# IO_Board.net
KiCad netlist of a schematic drawn in Altium Designer
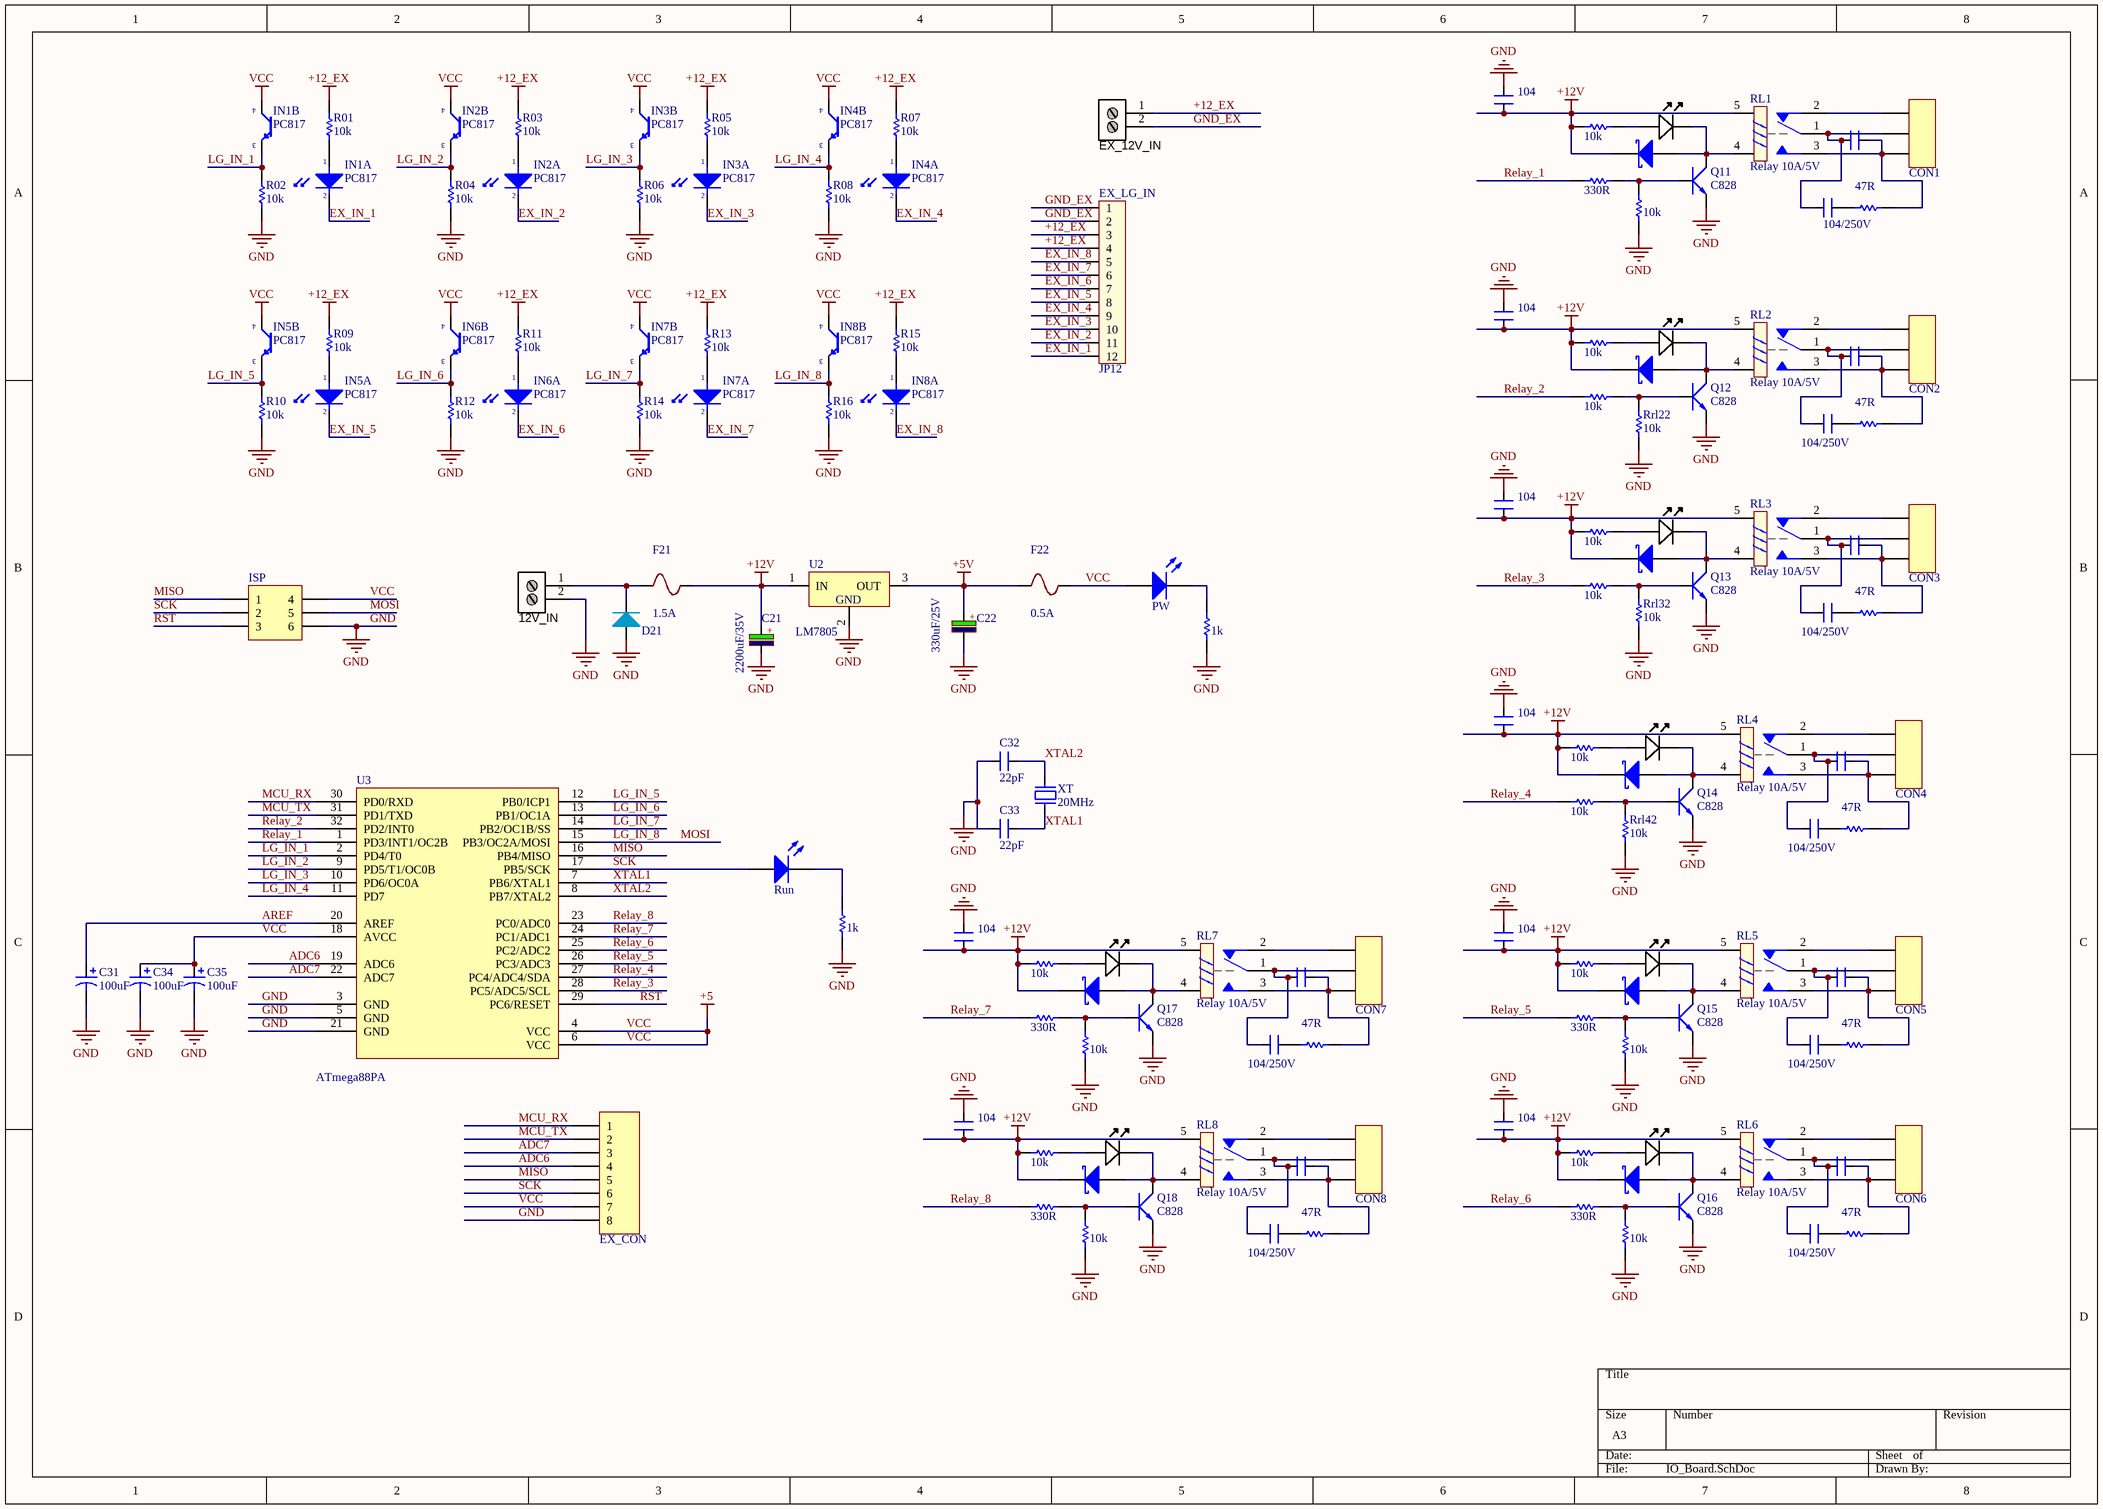
[diagram p0: IO_Board.SchDoc]

(export (version "E")
  (design (tool "Eeschema 10.0.6"))
  (components
    (comp (ref "12V_IN")
      (value "Stackable ScrewTerm")
      (footprint "2P_PCB_ScrewTerm_200mil")
      (description "Terminal Block Screw Type THT 2-Position 3.81mm pitch")
      (libsource (lib "PBL - Connectors") (part "2P_ScrewTerm_90S_3.81MM"))
    )
    (comp (ref "C21")
      (value "2200uF/35V")
      (footprint "heromap:CP_1000uF_25V")
      (description "Cap 1000uF/16V - 220uF/50V")
      (libsource (lib "heromap") (part "CP4"))
    )
    (comp (ref "C22")
      (value "330uF/25V")
      (footprint "heromap:CP1.5/3.4")
      (description "Cap 1000uF/16V - 220uF/50V")
      (libsource (lib "heromap") (part "CP4"))
    )
    (comp (ref "C31")
      (value "100uF")
      (footprint "CAPC2012N_F")
      (fields (field (name "Comment") "Cap"))
      (libsource (lib "Tuan") (part "Cap"))
    )
    (comp (ref "C32")
      (value "22pF")
      (footprint "CAPC1608N")
      (fields (field (name "Comment") "CAP NP"))
      (libsource (lib "Tuan") (part "CAP NP"))
    )
    (comp (ref "C33")
      (value "22pF")
      (footprint "CAPC1608N")
      (fields (field (name "Comment") "CAP NP"))
      (libsource (lib "Tuan") (part "CAP NP"))
    )
    (comp (ref "C34")
      (value "100uF")
      (footprint "CAPC2012N_F")
      (fields (field (name "Comment") "Cap"))
      (libsource (lib "Tuan") (part "Cap"))
    )
    (comp (ref "C35")
      (value "100uF")
      (footprint "CAPC2012N_F")
      (fields (field (name "Comment") "Cap"))
      (libsource (lib "Tuan") (part "Cap"))
    )
    (comp (ref "CON1")
      (value "3P_ScrewTerm_200mil")
      (footprint "3P_ScrewTerm_200mil")
      (libsource (lib "Tuan") (part "3P_ScrewTerm_200mil"))
    )
    (comp (ref "CON2")
      (value "3P_ScrewTerm_200mil")
      (footprint "3P_ScrewTerm_200mil")
      (libsource (lib "Tuan") (part "3P_ScrewTerm_200mil"))
    )
    (comp (ref "CON3")
      (value "3P_ScrewTerm_200mil")
      (footprint "3P_ScrewTerm_200mil")
      (libsource (lib "Tuan") (part "3P_ScrewTerm_200mil"))
    )
    (comp (ref "CON4")
      (value "3P_ScrewTerm_200mil")
      (footprint "3P_ScrewTerm_200mil")
      (libsource (lib "Tuan") (part "3P_ScrewTerm_200mil"))
    )
    (comp (ref "CON5")
      (value "3P_ScrewTerm_200mil")
      (footprint "3P_ScrewTerm_200mil")
      (libsource (lib "Tuan") (part "3P_ScrewTerm_200mil"))
    )
    (comp (ref "CON6")
      (value "3P_ScrewTerm_200mil")
      (footprint "3P_ScrewTerm_200mil")
      (libsource (lib "Tuan") (part "3P_ScrewTerm_200mil"))
    )
    (comp (ref "CON7")
      (value "3P_ScrewTerm_200mil")
      (footprint "3P_ScrewTerm_200mil")
      (libsource (lib "Tuan") (part "3P_ScrewTerm_200mil"))
    )
    (comp (ref "CON8")
      (value "3P_ScrewTerm_200mil")
      (footprint "3P_ScrewTerm_200mil")
      (libsource (lib "Tuan") (part "3P_ScrewTerm_200mil"))
    )
    (comp (ref "Crl1")
      (value "104")
      (footprint "CAPC2012N_F")
      (fields (field (name "Comment") "CAP NP"))
      (libsource (lib "Tuan") (part "CAP NP"))
    )
    (comp (ref "Crl2")
      (value "104")
      (footprint "CAPC2012N_F")
      (fields (field (name "Comment") "CAP NP"))
      (libsource (lib "Tuan") (part "CAP NP"))
    )
    (comp (ref "Crl3")
      (value "104")
      (footprint "CAPC2012N_F")
      (fields (field (name "Comment") "CAP NP"))
      (libsource (lib "Tuan") (part "CAP NP"))
    )
    (comp (ref "Crl4")
      (value "104")
      (footprint "CAPC2012N_F")
      (fields (field (name "Comment") "CAP NP"))
      (libsource (lib "Tuan") (part "CAP NP"))
    )
    (comp (ref "Crl5")
      (value "104")
      (footprint "CAPC2012N_F")
      (fields (field (name "Comment") "CAP NP"))
      (libsource (lib "Tuan") (part "CAP NP"))
    )
    (comp (ref "Crl6")
      (value "104")
      (footprint "CAPC2012N_F")
      (fields (field (name "Comment") "CAP NP"))
      (libsource (lib "Tuan") (part "CAP NP"))
    )
    (comp (ref "Crl7")
      (value "104")
      (footprint "CAPC2012N_F")
      (fields (field (name "Comment") "CAP NP"))
      (libsource (lib "Tuan") (part "CAP NP"))
    )
    (comp (ref "Crl8")
      (value "104")
      (footprint "CAPC2012N_F")
      (fields (field (name "Comment") "CAP NP"))
      (libsource (lib "Tuan") (part "CAP NP"))
    )
    (comp (ref "Csub1")
      (value "104/250V")
      (footprint "CAPMF12.5x4.5x9.0x10mmLS")
      (fields (field (name "Comment") "CAP NP"))
      (libsource (lib "Tuan") (part "CAP NP"))
    )
    (comp (ref "Csub2")
      (value "104/250V")
      (footprint "CAPMF12.5x4.5x9.0x10mmLS")
      (fields (field (name "Comment") "CAP NP"))
      (libsource (lib "Tuan") (part "CAP NP"))
    )
    (comp (ref "Csub3")
      (value "104/250V")
      (footprint "CAPMF12.5x4.5x9.0x10mmLS")
      (fields (field (name "Comment") "CAP NP"))
      (libsource (lib "Tuan") (part "CAP NP"))
    )
    (comp (ref "Csub4")
      (value "104/250V")
      (footprint "CAPMF12.5x4.5x9.0x10mmLS")
      (fields (field (name "Comment") "CAP NP"))
      (libsource (lib "Tuan") (part "CAP NP"))
    )
    (comp (ref "Csub5")
      (value "104/250V")
      (footprint "CAPMF12.5x4.5x9.0x10mmLS")
      (fields (field (name "Comment") "CAP NP"))
      (libsource (lib "Tuan") (part "CAP NP"))
    )
    (comp (ref "Csub6")
      (value "104/250V")
      (footprint "CAPMF12.5x4.5x9.0x10mmLS")
      (fields (field (name "Comment") "CAP NP"))
      (libsource (lib "Tuan") (part "CAP NP"))
    )
    (comp (ref "Csub7")
      (value "104/250V")
      (footprint "CAPMF12.5x4.5x9.0x10mmLS")
      (fields (field (name "Comment") "CAP NP"))
      (libsource (lib "Tuan") (part "CAP NP"))
    )
    (comp (ref "Csub8")
      (value "104/250V")
      (footprint "CAPMF12.5x4.5x9.0x10mmLS")
      (fields (field (name "Comment") "CAP NP"))
      (libsource (lib "Tuan") (part "CAP NP"))
    )
    (comp (ref "D11") (value "Diode") (footprint "DO-214AC") (libsource (lib "Tuan") (part "Diode")))
    (comp (ref "D12") (value "Diode") (footprint "DO-214AC") (libsource (lib "Tuan") (part "Diode")))
    (comp (ref "D13") (value "Diode") (footprint "DO-214AC") (libsource (lib "Tuan") (part "Diode")))
    (comp (ref "D14") (value "Diode") (footprint "DO-214AC") (libsource (lib "Tuan") (part "Diode")))
    (comp (ref "D15") (value "Diode") (footprint "DO-214AC") (libsource (lib "Tuan") (part "Diode")))
    (comp (ref "D16") (value "Diode") (footprint "DO-214AC") (libsource (lib "Tuan") (part "Diode")))
    (comp (ref "D17") (value "Diode") (footprint "DO-214AC") (libsource (lib "Tuan") (part "Diode")))
    (comp (ref "D18") (value "Diode") (footprint "DO-214AC") (libsource (lib "Tuan") (part "Diode")))
    (comp (ref "D21") (value "Diode") (footprint "Diode 3A") (libsource (lib "") (part "Diode_1")))
    (comp (ref "E1")
      (value "Blue")
      (footprint "LED-0805-A")
      (description "LED 0805 SMD Blue 100mcd 470nm")
      (libsource (lib "PBL - Light Sources") (part "LED_SMD_Blue_0805_100mcd"))
    )
    (comp (ref "E2")
      (value "Blue")
      (footprint "LED-0805-A")
      (description "LED 0805 SMD Blue 100mcd 470nm")
      (libsource (lib "PBL - Light Sources") (part "LED_SMD_Blue_0805_100mcd"))
    )
    (comp (ref "E3")
      (value "Blue")
      (footprint "LED-0805-A")
      (description "LED 0805 SMD Blue 100mcd 470nm")
      (libsource (lib "PBL - Light Sources") (part "LED_SMD_Blue_0805_100mcd"))
    )
    (comp (ref "E4")
      (value "Blue")
      (footprint "LED-0805-A")
      (description "LED 0805 SMD Blue 100mcd 470nm")
      (libsource (lib "PBL - Light Sources") (part "LED_SMD_Blue_0805_100mcd"))
    )
    (comp (ref "E5")
      (value "Blue")
      (footprint "LED-0805-A")
      (description "LED 0805 SMD Blue 100mcd 470nm")
      (libsource (lib "PBL - Light Sources") (part "LED_SMD_Blue_0805_100mcd"))
    )
    (comp (ref "E6")
      (value "Blue")
      (footprint "LED-0805-A")
      (description "LED 0805 SMD Blue 100mcd 470nm")
      (libsource (lib "PBL - Light Sources") (part "LED_SMD_Blue_0805_100mcd"))
    )
    (comp (ref "E7")
      (value "Blue")
      (footprint "LED-0805-A")
      (description "LED 0805 SMD Blue 100mcd 470nm")
      (libsource (lib "PBL - Light Sources") (part "LED_SMD_Blue_0805_100mcd"))
    )
    (comp (ref "E8")
      (value "Blue")
      (footprint "LED-0805-A")
      (description "LED 0805 SMD Blue 100mcd 470nm")
      (libsource (lib "PBL - Light Sources") (part "LED_SMD_Blue_0805_100mcd"))
    )
    (comp (ref "EX_12V_IN")
      (value "Stackable ScrewTerm")
      (footprint "2P_PCB_ScrewTerm_200mil")
      (description "Terminal Block Screw Type THT 2-Position 3.81mm pitch")
      (libsource (lib "PBL - Connectors") (part "2P_ScrewTerm_90S_3.81MM"))
    )
    (comp (ref "EX_CON")
      (value "Header 8")
      (footprint "heromap:HDR1X8")
      (description "Header, 8-Pin")
      (fields (field (name "PUBLISHER") "Altium Limited"))
      (libsource (lib "heromap") (part "Header 8"))
    )
    (comp (ref "EX_LG_IN")
      (value "JP12")
      (footprint "12P_ScrewTerm_200mil")
      (description "Connector 12")
      (libsource (lib "heromap") (part "Con12"))
    )
    (comp (ref "F21") (value "1.5A") (footprint "FUSE_SR-5-BK") (libsource (lib "Tuan") (part "Fuse")))
    (comp (ref "F22") (value "0.5A") (footprint "RESC2012N_ZERO") (libsource (lib "Tuan") (part "Fuse")))
    (comp (ref "IN1") (value "PC817") (footprint "DIP4/W0.3") (libsource (lib "Tuan") (part "Opto")))
    (comp (ref "IN2") (value "PC817") (footprint "DIP4/W0.3") (libsource (lib "Tuan") (part "Opto")))
    (comp (ref "IN3") (value "PC817") (footprint "DIP4/W0.3") (libsource (lib "Tuan") (part "Opto")))
    (comp (ref "IN4") (value "PC817") (footprint "DIP4/W0.3") (libsource (lib "Tuan") (part "Opto")))
    (comp (ref "IN5") (value "PC817") (footprint "DIP4/W0.3") (libsource (lib "Tuan") (part "Opto")))
    (comp (ref "IN6") (value "PC817") (footprint "DIP4/W0.3") (libsource (lib "Tuan") (part "Opto")))
    (comp (ref "IN7") (value "PC817") (footprint "DIP4/W0.3") (libsource (lib "Tuan") (part "Opto")))
    (comp (ref "IN8") (value "PC817") (footprint "DIP4/W0.3") (libsource (lib "Tuan") (part "Opto")))
    (comp (ref "ISP")
      (value "Header 3X2A")
      (footprint "HDR2X3_CEN")
      (description "Header, 3-Pin, Dual row")
      (fields (field (name "PUBLISHER") "Altium Limited"))
      (libsource (lib "Miscellaneous Connectors") (part "Header 3X2A"))
    )
    (comp (ref "MOV1")
      (value "CAP NP")
      (footprint "CAPC500P450250X550")
      (libsource (lib "Tuan") (part "CAP NP"))
    )
    (comp (ref "MOV2")
      (value "CAP NP")
      (footprint "CAPC500P450250X550")
      (libsource (lib "Tuan") (part "CAP NP"))
    )
    (comp (ref "MOV3")
      (value "CAP NP")
      (footprint "CAPC500P450250X550")
      (libsource (lib "Tuan") (part "CAP NP"))
    )
    (comp (ref "MOV4")
      (value "CAP NP")
      (footprint "CAPC500P450250X550")
      (libsource (lib "Tuan") (part "CAP NP"))
    )
    (comp (ref "MOV5")
      (value "CAP NP")
      (footprint "CAPC500P450250X550")
      (libsource (lib "Tuan") (part "CAP NP"))
    )
    (comp (ref "MOV6")
      (value "CAP NP")
      (footprint "CAPC500P450250X550")
      (libsource (lib "Tuan") (part "CAP NP"))
    )
    (comp (ref "MOV7")
      (value "CAP NP")
      (footprint "CAPC500P450250X550")
      (libsource (lib "Tuan") (part "CAP NP"))
    )
    (comp (ref "MOV8")
      (value "CAP NP")
      (footprint "CAPC500P450250X550")
      (libsource (lib "Tuan") (part "CAP NP"))
    )
    (comp (ref "PW") (value "Led") (footprint "LED 5mm RED") (libsource (lib "Tuan") (part "Led")))
    (comp (ref "Q11")
      (value "C828")
      (footprint "SOT23 TOP")
      (description "Transistor C828 C1815....")
      (libsource (lib "Tuan") (part "NPN"))
    )
    (comp (ref "Q12")
      (value "C828")
      (footprint "SOT23 TOP")
      (description "Transistor C828 C1815....")
      (libsource (lib "Tuan") (part "NPN"))
    )
    (comp (ref "Q13")
      (value "C828")
      (footprint "SOT23 TOP")
      (description "Transistor C828 C1815....")
      (libsource (lib "Tuan") (part "NPN"))
    )
    (comp (ref "Q14")
      (value "C828")
      (footprint "SOT23 TOP")
      (description "Transistor C828 C1815....")
      (libsource (lib "Tuan") (part "NPN"))
    )
    (comp (ref "Q15")
      (value "C828")
      (footprint "SOT23 TOP")
      (description "Transistor C828 C1815....")
      (libsource (lib "Tuan") (part "NPN"))
    )
    (comp (ref "Q16")
      (value "C828")
      (footprint "SOT23 TOP")
      (description "Transistor C828 C1815....")
      (libsource (lib "Tuan") (part "NPN"))
    )
    (comp (ref "Q17")
      (value "C828")
      (footprint "SOT23 TOP")
      (description "Transistor C828 C1815....")
      (libsource (lib "Tuan") (part "NPN"))
    )
    (comp (ref "Q18")
      (value "C828")
      (footprint "SOT23 TOP")
      (description "Transistor C828 C1815....")
      (libsource (lib "Tuan") (part "NPN"))
    )
    (comp (ref "R01")
      (value "10k")
      (footprint "RESC1608N_ZERO")
      (fields (field (name "Comment") "Res"))
      (libsource (lib "Tuan") (part "Res"))
    )
    (comp (ref "R02")
      (value "10k")
      (footprint "RESC1608N_ZERO")
      (fields (field (name "Comment") "Res"))
      (libsource (lib "Tuan") (part "Res"))
    )
    (comp (ref "R03")
      (value "10k")
      (footprint "RESC1608N_ZERO")
      (fields (field (name "Comment") "Res"))
      (libsource (lib "Tuan") (part "Res"))
    )
    (comp (ref "R04")
      (value "10k")
      (footprint "RESC2012N_F")
      (fields (field (name "Comment") "Res"))
      (libsource (lib "Tuan") (part "Res"))
    )
    (comp (ref "R05")
      (value "10k")
      (footprint "RESC2012N_F")
      (fields (field (name "Comment") "Res"))
      (libsource (lib "Tuan") (part "Res"))
    )
    (comp (ref "R06")
      (value "10k")
      (footprint "RESC2012N_F")
      (fields (field (name "Comment") "Res"))
      (libsource (lib "Tuan") (part "Res"))
    )
    (comp (ref "R07")
      (value "10k")
      (footprint "RESC2012N_F")
      (fields (field (name "Comment") "Res"))
      (libsource (lib "Tuan") (part "Res"))
    )
    (comp (ref "R08")
      (value "10k")
      (footprint "RESC2012N_F")
      (fields (field (name "Comment") "Res"))
      (libsource (lib "Tuan") (part "Res"))
    )
    (comp (ref "R09")
      (value "10k")
      (footprint "RESC2012N_F")
      (fields (field (name "Comment") "Res"))
      (libsource (lib "Tuan") (part "Res"))
    )
    (comp (ref "R10")
      (value "10k")
      (footprint "RESC2012N_F")
      (fields (field (name "Comment") "Res"))
      (libsource (lib "Tuan") (part "Res"))
    )
    (comp (ref "R11")
      (value "10k")
      (footprint "RESC2012N_F")
      (fields (field (name "Comment") "Res"))
      (libsource (lib "Tuan") (part "Res"))
    )
    (comp (ref "R12")
      (value "10k")
      (footprint "RESC2012N_F")
      (fields (field (name "Comment") "Res"))
      (libsource (lib "Tuan") (part "Res"))
    )
    (comp (ref "R13")
      (value "10k")
      (footprint "RESC2012N_F")
      (fields (field (name "Comment") "Res"))
      (libsource (lib "Tuan") (part "Res"))
    )
    (comp (ref "R14")
      (value "10k")
      (footprint "RESC2012N_F")
      (fields (field (name "Comment") "Res"))
      (libsource (lib "Tuan") (part "Res"))
    )
    (comp (ref "R15")
      (value "10k")
      (footprint "RESC2012N_F")
      (fields (field (name "Comment") "Res"))
      (libsource (lib "Tuan") (part "Res"))
    )
    (comp (ref "R16")
      (value "10k")
      (footprint "RESC2012N_F")
      (fields (field (name "Comment") "Res"))
      (libsource (lib "Tuan") (part "Res"))
    )
    (comp (ref "R21")
      (value "1k")
      (footprint "RESC2012N_F")
      (fields (field (name "Comment") "Res_0805_1k"))
      (libsource (lib "Tuan") (part "Res"))
    )
    (comp (ref "R31")
      (value "1k")
      (footprint "RESC2012N_F")
      (fields (field (name "Comment") "Res_0805_1k"))
      (libsource (lib "Tuan") (part "Res"))
    )
    (comp (ref "RL1")
      (value "Relay 10A/5V")
      (footprint "RL_5PIN")
      (description "Relay SPDT,10A - 12VDC 5 Pin")
      (libsource (lib "syhaunguyen") (part "Relay 1"))
    )
    (comp (ref "RL2")
      (value "Relay 10A/5V")
      (footprint "RL_5PIN")
      (description "Relay SPDT,10A - 12VDC 5 Pin")
      (libsource (lib "syhaunguyen") (part "Relay 1"))
    )
    (comp (ref "RL3")
      (value "Relay 10A/5V")
      (footprint "RL_5PIN")
      (description "Relay SPDT,10A - 12VDC 5 Pin")
      (libsource (lib "syhaunguyen") (part "Relay 1"))
    )
    (comp (ref "RL4")
      (value "Relay 10A/5V")
      (footprint "RL_5PIN")
      (description "Relay SPDT,10A - 12VDC 5 Pin")
      (libsource (lib "syhaunguyen") (part "Relay 1"))
    )
    (comp (ref "RL5")
      (value "Relay 10A/5V")
      (footprint "RL_5PIN")
      (description "Relay SPDT,10A - 12VDC 5 Pin")
      (libsource (lib "syhaunguyen") (part "Relay 1"))
    )
    (comp (ref "RL6")
      (value "Relay 10A/5V")
      (footprint "RL_5PIN")
      (description "Relay SPDT,10A - 12VDC 5 Pin")
      (libsource (lib "syhaunguyen") (part "Relay 1"))
    )
    (comp (ref "RL7")
      (value "Relay 10A/5V")
      (footprint "RL_5PIN")
      (description "Relay SPDT,10A - 12VDC 5 Pin")
      (libsource (lib "syhaunguyen") (part "Relay 1"))
    )
    (comp (ref "RL8")
      (value "Relay 10A/5V")
      (footprint "RL_5PIN")
      (description "Relay SPDT,10A - 12VDC 5 Pin")
      (libsource (lib "syhaunguyen") (part "Relay 1"))
    )
    (comp (ref "Rl52")
      (value "10k")
      (footprint "RESC1608N_ZERO")
      (fields (field (name "Comment") "Res"))
      (libsource (lib "Tuan") (part "Res"))
    )
    (comp (ref "Rrl11")
      (value "330R")
      (footprint "RESC1608N_ZERO")
      (fields (field (name "Comment") "Res"))
      (libsource (lib "Tuan") (part "Res"))
    )
    (comp (ref "Rrl12")
      (value "10k")
      (footprint "RESC1608N_ZERO")
      (fields (field (name "Comment") "Res"))
      (libsource (lib "Tuan") (part "Res"))
    )
    (comp (ref "Rrl13")
      (value "10k")
      (footprint "RESC1608N_ZERO")
      (fields (field (name "Comment") "Res"))
      (libsource (lib "Tuan") (part "Res"))
    )
    (comp (ref "Rrl21")
      (value "10k")
      (footprint "RESC1608N_ZERO")
      (fields (field (name "Comment") "Res"))
      (libsource (lib "Tuan") (part "Res"))
    )
    (comp (ref "Rrl22")
      (value "10k")
      (footprint "RESC1608N_ZERO")
      (fields (field (name "Comment") "Res"))
      (libsource (lib "Tuan") (part "Res"))
    )
    (comp (ref "Rrl23")
      (value "10k")
      (footprint "RESC1608N_ZERO")
      (fields (field (name "Comment") "Res"))
      (libsource (lib "Tuan") (part "Res"))
    )
    (comp (ref "Rrl31")
      (value "10k")
      (footprint "RESC1608N_ZERO")
      (fields (field (name "Comment") "Res"))
      (libsource (lib "Tuan") (part "Res"))
    )
    (comp (ref "Rrl32")
      (value "10k")
      (footprint "RESC1608N_ZERO")
      (fields (field (name "Comment") "Res"))
      (libsource (lib "Tuan") (part "Res"))
    )
    (comp (ref "Rrl33")
      (value "10k")
      (footprint "RESC1608N_ZERO")
      (fields (field (name "Comment") "Res"))
      (libsource (lib "Tuan") (part "Res"))
    )
    (comp (ref "Rrl41")
      (value "10k")
      (footprint "RESC1608N_ZERO")
      (fields (field (name "Comment") "Res"))
      (libsource (lib "Tuan") (part "Res"))
    )
    (comp (ref "Rrl42")
      (value "10k")
      (footprint "RESC1608N_ZERO")
      (fields (field (name "Comment") "Res"))
      (libsource (lib "Tuan") (part "Res"))
    )
    (comp (ref "Rrl43")
      (value "10k")
      (footprint "RESC1608N_ZERO")
      (fields (field (name "Comment") "Res"))
      (libsource (lib "Tuan") (part "Res"))
    )
    (comp (ref "Rrl51")
      (value "330R")
      (footprint "RESC1608N_ZERO")
      (fields (field (name "Comment") "Res"))
      (libsource (lib "Tuan") (part "Res"))
    )
    (comp (ref "Rrl53")
      (value "10k")
      (footprint "RESC1608N_ZERO")
      (fields (field (name "Comment") "Res"))
      (libsource (lib "Tuan") (part "Res"))
    )
    (comp (ref "Rrl61")
      (value "330R")
      (footprint "RESC1608N_ZERO")
      (fields (field (name "Comment") "Res"))
      (libsource (lib "Tuan") (part "Res"))
    )
    (comp (ref "Rrl62")
      (value "10k")
      (footprint "RESC1608N_ZERO")
      (fields (field (name "Comment") "Res"))
      (libsource (lib "Tuan") (part "Res"))
    )
    (comp (ref "Rrl63")
      (value "10k")
      (footprint "RESC1608N_ZERO")
      (fields (field (name "Comment") "Res"))
      (libsource (lib "Tuan") (part "Res"))
    )
    (comp (ref "Rrl71")
      (value "330R")
      (footprint "RESC1608N_ZERO")
      (fields (field (name "Comment") "Res"))
      (libsource (lib "Tuan") (part "Res"))
    )
    (comp (ref "Rrl72")
      (value "10k")
      (footprint "RESC1608N_ZERO")
      (fields (field (name "Comment") "Res"))
      (libsource (lib "Tuan") (part "Res"))
    )
    (comp (ref "Rrl73")
      (value "10k")
      (footprint "RESC1608N_ZERO")
      (fields (field (name "Comment") "Res"))
      (libsource (lib "Tuan") (part "Res"))
    )
    (comp (ref "Rrl81")
      (value "330R")
      (footprint "RESC1608N_ZERO")
      (fields (field (name "Comment") "Res"))
      (libsource (lib "Tuan") (part "Res"))
    )
    (comp (ref "Rrl82")
      (value "10k")
      (footprint "RESC1608N_ZERO")
      (fields (field (name "Comment") "Res"))
      (libsource (lib "Tuan") (part "Res"))
    )
    (comp (ref "Rrl83")
      (value "10k")
      (footprint "RESC1608N_ZERO")
      (fields (field (name "Comment") "Res"))
      (libsource (lib "Tuan") (part "Res"))
    )
    (comp (ref "Rsub1")
      (value "47R")
      (footprint "RESTH_AXIAL-0.4")
      (fields (field (name "Comment") "Res"))
      (libsource (lib "Tuan") (part "Res"))
    )
    (comp (ref "Rsub2")
      (value "47R")
      (footprint "RESTH_AXIAL-0.4")
      (fields (field (name "Comment") "Res"))
      (libsource (lib "Tuan") (part "Res"))
    )
    (comp (ref "Rsub3")
      (value "47R")
      (footprint "RESTH_AXIAL-0.4")
      (fields (field (name "Comment") "Res"))
      (libsource (lib "Tuan") (part "Res"))
    )
    (comp (ref "Rsub4")
      (value "47R")
      (footprint "RESTH_AXIAL-0.4")
      (fields (field (name "Comment") "Res"))
      (libsource (lib "Tuan") (part "Res"))
    )
    (comp (ref "Rsub5")
      (value "47R")
      (footprint "RESTH_AXIAL-0.4")
      (fields (field (name "Comment") "Res"))
      (libsource (lib "Tuan") (part "Res"))
    )
    (comp (ref "Rsub6")
      (value "47R")
      (footprint "RESTH_AXIAL-0.4")
      (fields (field (name "Comment") "Res"))
      (libsource (lib "Tuan") (part "Res"))
    )
    (comp (ref "Rsub7")
      (value "47R")
      (footprint "RESTH_AXIAL-0.4")
      (fields (field (name "Comment") "Res"))
      (libsource (lib "Tuan") (part "Res"))
    )
    (comp (ref "Rsub8")
      (value "47R")
      (footprint "RESTH_AXIAL-0.4")
      (fields (field (name "Comment") "Res"))
      (libsource (lib "Tuan") (part "Res"))
    )
    (comp (ref "Run") (value "Led") (footprint "LED 5mm RED") (libsource (lib "Tuan") (part "Led")))
    (comp (ref "U2") (value "LM7805") (footprint "TO-220") (libsource (lib "Tuan") (part "LM78xx")))
    (comp (ref "U3")
      (value "ATmega88PA")
      (footprint "32PIN")
      (description "ATmega48/168/328")
      (libsource (lib "Tuan") (part "ATmega48/168/328"))
    )
    (comp (ref "XT") (value "20MHz") (footprint "XT2") (libsource (lib "Tuan") (part "Crystal")))
  )
  (nets
    (net (code "1") (name "+5") (class "Default")
      (node (ref "C34") (pin "1") (pinfunction "1_1") (pintype "passive"))
      (node (ref "C35") (pin "1") (pinfunction "1_1") (pintype "passive"))
      (node (ref "EX_CON") (pin "7") (pinfunction "7_7") (pintype "passive"))
      (node (ref "F22") (pin "2") (pinfunction "2_2") (pintype "passive"))
      (node (ref "IN1") (pin "4") (pinfunction "C_4") (pintype "passive"))
      (node (ref "IN2") (pin "4") (pinfunction "C_4") (pintype "passive"))
      (node (ref "IN3") (pin "4") (pinfunction "C_4") (pintype "passive"))
      (node (ref "IN4") (pin "4") (pinfunction "C_4") (pintype "passive"))
      (node (ref "IN5") (pin "4") (pinfunction "C_4") (pintype "passive"))
      (node (ref "IN6") (pin "4") (pinfunction "C_4") (pintype "passive"))
      (node (ref "IN7") (pin "4") (pinfunction "C_4") (pintype "passive"))
      (node (ref "IN8") (pin "4") (pinfunction "C_4") (pintype "passive"))
      (node (ref "ISP") (pin "4") (pinfunction "4_4") (pintype "passive"))
      (node (ref "PW") (pin "1") (pinfunction "A_1") (pintype "passive"))
      (node (ref "U3") (pin "18") (pinfunction "AVCC_18") (pintype "passive"))
      (node (ref "U3") (pin "4") (pinfunction "VCC_4") (pintype "passive"))
      (node (ref "U3") (pin "6") (pinfunction "VCC_6") (pintype "passive"))
    )
    (net (code "2") (name "+5V") (class "Default")
      (node (ref "C22") (pin "1") (pinfunction "1_1") (pintype "passive"))
      (node (ref "F22") (pin "1") (pinfunction "1_1") (pintype "passive"))
      (node (ref "U2") (pin "3") (pinfunction "OUT_3") (pintype "passive"))
    )
    (net (code "3") (name "+12V") (class "Default")
      (node (ref "C21") (pin "1") (pinfunction "1_1") (pintype "passive"))
      (node (ref "Crl1") (pin "1") (pinfunction "1_1") (pintype "passive"))
      (node (ref "Crl2") (pin "1") (pinfunction "1_1") (pintype "passive"))
      (node (ref "Crl3") (pin "1") (pinfunction "1_1") (pintype "passive"))
      (node (ref "Crl4") (pin "1") (pinfunction "1_1") (pintype "passive"))
      (node (ref "Crl5") (pin "1") (pinfunction "1_1") (pintype "passive"))
      (node (ref "Crl6") (pin "1") (pinfunction "1_1") (pintype "passive"))
      (node (ref "Crl7") (pin "1") (pinfunction "1_1") (pintype "passive"))
      (node (ref "Crl8") (pin "1") (pinfunction "1_1") (pintype "passive"))
      (node (ref "D11") (pin "2") (pinfunction "K_2") (pintype "passive"))
      (node (ref "D12") (pin "2") (pinfunction "K_2") (pintype "passive"))
      (node (ref "D13") (pin "2") (pinfunction "K_2") (pintype "passive"))
      (node (ref "D14") (pin "2") (pinfunction "K_2") (pintype "passive"))
      (node (ref "D15") (pin "2") (pinfunction "K_2") (pintype "passive"))
      (node (ref "D16") (pin "2") (pinfunction "K_2") (pintype "passive"))
      (node (ref "D17") (pin "2") (pinfunction "K_2") (pintype "passive"))
      (node (ref "D18") (pin "2") (pinfunction "K_2") (pintype "passive"))
      (node (ref "F21") (pin "2") (pinfunction "2_2") (pintype "passive"))
      (node (ref "RL1") (pin "5") (pinfunction "5_5") (pintype "passive"))
      (node (ref "RL2") (pin "5") (pinfunction "5_5") (pintype "passive"))
      (node (ref "RL3") (pin "5") (pinfunction "5_5") (pintype "passive"))
      (node (ref "RL4") (pin "5") (pinfunction "5_5") (pintype "passive"))
      (node (ref "RL5") (pin "5") (pinfunction "5_5") (pintype "passive"))
      (node (ref "RL6") (pin "5") (pinfunction "5_5") (pintype "passive"))
      (node (ref "RL7") (pin "5") (pinfunction "5_5") (pintype "passive"))
      (node (ref "RL8") (pin "5") (pinfunction "5_5") (pintype "passive"))
      (node (ref "Rrl13") (pin "2") (pinfunction "2_2") (pintype "passive"))
      (node (ref "Rrl23") (pin "2") (pinfunction "2_2") (pintype "passive"))
      (node (ref "Rrl33") (pin "2") (pinfunction "2_2") (pintype "passive"))
      (node (ref "Rrl43") (pin "2") (pinfunction "2_2") (pintype "passive"))
      (node (ref "Rrl53") (pin "2") (pinfunction "2_2") (pintype "passive"))
      (node (ref "Rrl63") (pin "2") (pinfunction "2_2") (pintype "passive"))
      (node (ref "Rrl73") (pin "2") (pinfunction "2_2") (pintype "passive"))
      (node (ref "Rrl83") (pin "2") (pinfunction "2_2") (pintype "passive"))
      (node (ref "U2") (pin "1") (pinfunction "IN_1") (pintype "passive"))
    )
    (net (code "4") (name "+12_EX") (class "Default")
      (node (ref "EX_12V_IN") (pin "1") (pinfunction "1_1") (pintype "passive"))
      (node (ref "EX_LG_IN") (pin "3") (pinfunction "3_3") (pintype "passive"))
      (node (ref "EX_LG_IN") (pin "4") (pinfunction "4_4") (pintype "passive"))
      (node (ref "R01") (pin "2") (pinfunction "2_2") (pintype "passive"))
      (node (ref "R03") (pin "2") (pinfunction "2_2") (pintype "passive"))
      (node (ref "R05") (pin "2") (pinfunction "2_2") (pintype "passive"))
      (node (ref "R07") (pin "2") (pinfunction "2_2") (pintype "passive"))
      (node (ref "R09") (pin "2") (pinfunction "2_2") (pintype "passive"))
      (node (ref "R11") (pin "2") (pinfunction "2_2") (pintype "passive"))
      (node (ref "R13") (pin "2") (pinfunction "2_2") (pintype "passive"))
      (node (ref "R15") (pin "2") (pinfunction "2_2") (pintype "passive"))
    )
    (net (code "5") (name "/ADC6") (class "Default")
      (node (ref "EX_CON") (pin "4") (pinfunction "4_4") (pintype "passive"))
      (node (ref "U3") (pin "19") (pinfunction "ADC6_19") (pintype "passive"))
    )
    (net (code "6") (name "/ADC7") (class "Default")
      (node (ref "EX_CON") (pin "3") (pinfunction "3_3") (pintype "passive"))
      (node (ref "U3") (pin "22") (pinfunction "ADC7_22") (pintype "passive"))
    )
    (net (code "7") (name "/AREF") (class "Default")
      (node (ref "C31") (pin "1") (pinfunction "1_1") (pintype "passive"))
      (node (ref "U3") (pin "20") (pinfunction "AREF_20") (pintype "passive"))
    )
    (net (code "8") (name "/EX_IN_1") (class "Default")
      (node (ref "EX_LG_IN") (pin "12") (pinfunction "12_12") (pintype "passive"))
      (node (ref "IN1") (pin "2") (pinfunction "K_2") (pintype "passive"))
    )
    (net (code "9") (name "/EX_IN_2") (class "Default")
      (node (ref "EX_LG_IN") (pin "11") (pinfunction "11_11") (pintype "passive"))
      (node (ref "IN2") (pin "2") (pinfunction "K_2") (pintype "passive"))
    )
    (net (code "10") (name "/EX_IN_3") (class "Default")
      (node (ref "EX_LG_IN") (pin "10") (pinfunction "10_10") (pintype "passive"))
      (node (ref "IN3") (pin "2") (pinfunction "K_2") (pintype "passive"))
    )
    (net (code "11") (name "/EX_IN_4") (class "Default")
      (node (ref "EX_LG_IN") (pin "9") (pinfunction "9_9") (pintype "passive"))
      (node (ref "IN4") (pin "2") (pinfunction "K_2") (pintype "passive"))
    )
    (net (code "12") (name "/EX_IN_5") (class "Default")
      (node (ref "EX_LG_IN") (pin "8") (pinfunction "8_8") (pintype "passive"))
      (node (ref "IN5") (pin "2") (pinfunction "K_2") (pintype "passive"))
    )
    (net (code "13") (name "/EX_IN_6") (class "Default")
      (node (ref "EX_LG_IN") (pin "7") (pinfunction "7_7") (pintype "passive"))
      (node (ref "IN6") (pin "2") (pinfunction "K_2") (pintype "passive"))
    )
    (net (code "14") (name "/EX_IN_7") (class "Default")
      (node (ref "EX_LG_IN") (pin "6") (pinfunction "6_6") (pintype "passive"))
      (node (ref "IN7") (pin "2") (pinfunction "K_2") (pintype "passive"))
    )
    (net (code "15") (name "/EX_IN_8") (class "Default")
      (node (ref "EX_LG_IN") (pin "5") (pinfunction "5_5") (pintype "passive"))
      (node (ref "IN8") (pin "2") (pinfunction "K_2") (pintype "passive"))
    )
    (net (code "16") (name "/GND_EX") (class "Default")
      (node (ref "EX_12V_IN") (pin "2") (pinfunction "2_2") (pintype "passive"))
      (node (ref "EX_LG_IN") (pin "1") (pinfunction "1_1") (pintype "passive"))
      (node (ref "EX_LG_IN") (pin "2") (pinfunction "2_2") (pintype "passive"))
    )
    (net (code "17") (name "/LG_IN_1") (class "Default")
      (node (ref "IN1") (pin "3") (pinfunction "E_3") (pintype "passive"))
      (node (ref "R02") (pin "2") (pinfunction "2_2") (pintype "passive"))
      (node (ref "U3") (pin "2") (pinfunction "PD4/T0_2") (pintype "passive"))
    )
    (net (code "18") (name "/LG_IN_2") (class "Default")
      (node (ref "IN2") (pin "3") (pinfunction "E_3") (pintype "passive"))
      (node (ref "R04") (pin "2") (pinfunction "2_2") (pintype "passive"))
      (node (ref "U3") (pin "9") (pinfunction "PD5/T1/OC0B_9") (pintype "passive"))
    )
    (net (code "19") (name "/LG_IN_3") (class "Default")
      (node (ref "IN3") (pin "3") (pinfunction "E_3") (pintype "passive"))
      (node (ref "R06") (pin "2") (pinfunction "2_2") (pintype "passive"))
      (node (ref "U3") (pin "10") (pinfunction "PD6/OC0A_10") (pintype "passive"))
    )
    (net (code "20") (name "/LG_IN_4") (class "Default")
      (node (ref "IN4") (pin "3") (pinfunction "E_3") (pintype "passive"))
      (node (ref "R08") (pin "2") (pinfunction "2_2") (pintype "passive"))
      (node (ref "U3") (pin "11") (pinfunction "PD7_11") (pintype "passive"))
    )
    (net (code "21") (name "/LG_IN_5") (class "Default")
      (node (ref "IN5") (pin "3") (pinfunction "E_3") (pintype "passive"))
      (node (ref "R10") (pin "2") (pinfunction "2_2") (pintype "passive"))
      (node (ref "U3") (pin "12") (pinfunction "PB0/ICP1_12") (pintype "passive"))
    )
    (net (code "22") (name "/LG_IN_6") (class "Default")
      (node (ref "IN6") (pin "3") (pinfunction "E_3") (pintype "passive"))
      (node (ref "R12") (pin "2") (pinfunction "2_2") (pintype "passive"))
      (node (ref "U3") (pin "13") (pinfunction "PB1/OC1A_13") (pintype "passive"))
    )
    (net (code "23") (name "/LG_IN_7") (class "Default")
      (node (ref "IN7") (pin "3") (pinfunction "E_3") (pintype "passive"))
      (node (ref "R14") (pin "2") (pinfunction "2_2") (pintype "passive"))
      (node (ref "U3") (pin "14") (pinfunction "PB2/OC1B/SS_14") (pintype "passive"))
    )
    (net (code "24") (name "/LG_IN_8") (class "Default")
      (node (ref "IN8") (pin "3") (pinfunction "E_3") (pintype "passive"))
      (node (ref "ISP") (pin "5") (pinfunction "5_5") (pintype "passive"))
      (node (ref "R16") (pin "2") (pinfunction "2_2") (pintype "passive"))
      (node (ref "U3") (pin "15") (pinfunction "PB3/OC2A/MOSI_15") (pintype "passive"))
    )
    (net (code "25") (name "/MCU_RX") (class "Default")
      (node (ref "EX_CON") (pin "1") (pinfunction "1_1") (pintype "passive"))
      (node (ref "U3") (pin "30") (pinfunction "PD0/RXD_30") (pintype "passive"))
    )
    (net (code "26") (name "/MCU_TX") (class "Default")
      (node (ref "EX_CON") (pin "2") (pinfunction "2_2") (pintype "passive"))
      (node (ref "U3") (pin "31") (pinfunction "PD1/TXD_31") (pintype "passive"))
    )
    (net (code "27") (name "/MISO") (class "Default")
      (node (ref "EX_CON") (pin "5") (pinfunction "5_5") (pintype "passive"))
      (node (ref "ISP") (pin "1") (pinfunction "1_1") (pintype "passive"))
      (node (ref "U3") (pin "16") (pinfunction "PB4/MISO_16") (pintype "passive"))
    )
    (net (code "28") (name "/RST") (class "Default")
      (node (ref "ISP") (pin "3") (pinfunction "3_3") (pintype "passive"))
      (node (ref "U3") (pin "29") (pinfunction "PC6/RESET_29") (pintype "passive"))
    )
    (net (code "29") (name "/Relay_1") (class "Default")
      (node (ref "Rrl11") (pin "1") (pinfunction "1_1") (pintype "passive"))
      (node (ref "U3") (pin "1") (pinfunction "PD3/INT1/OC2B_1") (pintype "passive"))
    )
    (net (code "30") (name "/Relay_2") (class "Default")
      (node (ref "Rrl21") (pin "1") (pinfunction "1_1") (pintype "passive"))
      (node (ref "U3") (pin "32") (pinfunction "PD2/INT0_32") (pintype "passive"))
    )
    (net (code "31") (name "/Relay_3") (class "Default")
      (node (ref "Rrl31") (pin "1") (pinfunction "1_1") (pintype "passive"))
      (node (ref "U3") (pin "28") (pinfunction "PC5/ADC5/SCL_28") (pintype "passive"))
    )
    (net (code "32") (name "/Relay_4") (class "Default")
      (node (ref "Rrl41") (pin "1") (pinfunction "1_1") (pintype "passive"))
      (node (ref "U3") (pin "27") (pinfunction "PC4/ADC4/SDA_27") (pintype "passive"))
    )
    (net (code "33") (name "/Relay_5") (class "Default")
      (node (ref "Rrl51") (pin "1") (pinfunction "1_1") (pintype "passive"))
      (node (ref "U3") (pin "26") (pinfunction "PC3/ADC3_26") (pintype "passive"))
    )
    (net (code "34") (name "/Relay_6") (class "Default")
      (node (ref "Rrl61") (pin "1") (pinfunction "1_1") (pintype "passive"))
      (node (ref "U3") (pin "25") (pinfunction "PC2/ADC2_25") (pintype "passive"))
    )
    (net (code "35") (name "/Relay_7") (class "Default")
      (node (ref "Rrl71") (pin "1") (pinfunction "1_1") (pintype "passive"))
      (node (ref "U3") (pin "24") (pinfunction "PC1/ADC1_24") (pintype "passive"))
    )
    (net (code "36") (name "/Relay_8") (class "Default")
      (node (ref "Rrl81") (pin "1") (pinfunction "1_1") (pintype "passive"))
      (node (ref "U3") (pin "23") (pinfunction "PC0/ADC0_23") (pintype "passive"))
    )
    (net (code "37") (name "/SCK") (class "Default")
      (node (ref "EX_CON") (pin "6") (pinfunction "6_6") (pintype "passive"))
      (node (ref "ISP") (pin "2") (pinfunction "2_2") (pintype "passive"))
      (node (ref "Run") (pin "1") (pinfunction "A_1") (pintype "passive"))
      (node (ref "U3") (pin "17") (pinfunction "PB5/SCK_17") (pintype "passive"))
    )
    (net (code "38") (name "/XTAL1") (class "Default")
      (node (ref "C33") (pin "1") (pinfunction "1_1") (pintype "passive"))
      (node (ref "U3") (pin "7") (pinfunction "PB6/XTAL1_7") (pintype "passive"))
      (node (ref "XT") (pin "1") (pinfunction "1_1") (pintype "passive"))
    )
    (net (code "39") (name "/XTAL2") (class "Default")
      (node (ref "C32") (pin "1") (pinfunction "1_1") (pintype "passive"))
      (node (ref "U3") (pin "8") (pinfunction "PB7/XTAL2_8") (pintype "passive"))
      (node (ref "XT") (pin "2") (pinfunction "2_2") (pintype "passive"))
    )
    (net (code "40") (name "GND") (class "Default")
      (node (ref "12V_IN") (pin "2") (pinfunction "2_2") (pintype "passive"))
      (node (ref "C21") (pin "2") (pinfunction "2_2") (pintype "passive"))
      (node (ref "C22") (pin "2") (pinfunction "2_2") (pintype "passive"))
      (node (ref "C31") (pin "2") (pinfunction "2_2") (pintype "passive"))
      (node (ref "C32") (pin "2") (pinfunction "2_2") (pintype "passive"))
      (node (ref "C33") (pin "2") (pinfunction "2_2") (pintype "passive"))
      (node (ref "C34") (pin "2") (pinfunction "2_2") (pintype "passive"))
      (node (ref "C35") (pin "2") (pinfunction "2_2") (pintype "passive"))
      (node (ref "Crl1") (pin "2") (pinfunction "2_2") (pintype "passive"))
      (node (ref "Crl2") (pin "2") (pinfunction "2_2") (pintype "passive"))
      (node (ref "Crl3") (pin "2") (pinfunction "2_2") (pintype "passive"))
      (node (ref "Crl4") (pin "2") (pinfunction "2_2") (pintype "passive"))
      (node (ref "Crl5") (pin "2") (pinfunction "2_2") (pintype "passive"))
      (node (ref "Crl6") (pin "2") (pinfunction "2_2") (pintype "passive"))
      (node (ref "Crl7") (pin "2") (pinfunction "2_2") (pintype "passive"))
      (node (ref "Crl8") (pin "2") (pinfunction "2_2") (pintype "passive"))
      (node (ref "D21") (pin "1") (pinfunction "A_1") (pintype "passive"))
      (node (ref "EX_CON") (pin "8") (pinfunction "8_8") (pintype "passive"))
      (node (ref "ISP") (pin "6") (pinfunction "6_6") (pintype "passive"))
      (node (ref "Q11") (pin "3") (pinfunction "E_3") (pintype "passive"))
      (node (ref "Q12") (pin "3") (pinfunction "E_3") (pintype "passive"))
      (node (ref "Q13") (pin "3") (pinfunction "E_3") (pintype "passive"))
      (node (ref "Q14") (pin "3") (pinfunction "E_3") (pintype "passive"))
      (node (ref "Q15") (pin "3") (pinfunction "E_3") (pintype "passive"))
      (node (ref "Q16") (pin "3") (pinfunction "E_3") (pintype "passive"))
      (node (ref "Q17") (pin "3") (pinfunction "E_3") (pintype "passive"))
      (node (ref "Q18") (pin "3") (pinfunction "E_3") (pintype "passive"))
      (node (ref "R02") (pin "1") (pinfunction "1_1") (pintype "passive"))
      (node (ref "R04") (pin "1") (pinfunction "1_1") (pintype "passive"))
      (node (ref "R06") (pin "1") (pinfunction "1_1") (pintype "passive"))
      (node (ref "R08") (pin "1") (pinfunction "1_1") (pintype "passive"))
      (node (ref "R10") (pin "1") (pinfunction "1_1") (pintype "passive"))
      (node (ref "R12") (pin "1") (pinfunction "1_1") (pintype "passive"))
      (node (ref "R14") (pin "1") (pinfunction "1_1") (pintype "passive"))
      (node (ref "R16") (pin "1") (pinfunction "1_1") (pintype "passive"))
      (node (ref "R21") (pin "2") (pinfunction "2_2") (pintype "passive"))
      (node (ref "R31") (pin "2") (pinfunction "2_2") (pintype "passive"))
      (node (ref "Rl52") (pin "1") (pinfunction "1_1") (pintype "passive"))
      (node (ref "Rrl12") (pin "1") (pinfunction "1_1") (pintype "passive"))
      (node (ref "Rrl22") (pin "1") (pinfunction "1_1") (pintype "passive"))
      (node (ref "Rrl32") (pin "1") (pinfunction "1_1") (pintype "passive"))
      (node (ref "Rrl42") (pin "1") (pinfunction "1_1") (pintype "passive"))
      (node (ref "Rrl62") (pin "1") (pinfunction "1_1") (pintype "passive"))
      (node (ref "Rrl72") (pin "1") (pinfunction "1_1") (pintype "passive"))
      (node (ref "Rrl82") (pin "1") (pinfunction "1_1") (pintype "passive"))
      (node (ref "U2") (pin "2") (pintype "passive"))
      (node (ref "U3") (pin "21") (pinfunction "GND_21") (pintype "power_in"))
      (node (ref "U3") (pin "3") (pinfunction "GND_3") (pintype "power_in"))
      (node (ref "U3") (pin "5") (pinfunction "GND_5") (pintype "power_in"))
    )
    (net (code "41") (name "Net-(CON1-Pad1)") (class "Default")
      (node (ref "CON1") (pin "1") (pinfunction "1_1") (pintype "passive"))
      (node (ref "RL1") (pin "2") (pinfunction "2_2") (pintype "passive"))
    )
    (net (code "42") (name "Net-(CON1-Pad2)") (class "Default")
      (node (ref "CON1") (pin "2") (pinfunction "2_2") (pintype "passive"))
      (node (ref "Csub1") (pin "2") (pinfunction "2_2") (pintype "passive"))
      (node (ref "MOV1") (pin "2") (pinfunction "2_2") (pintype "passive"))
      (node (ref "RL1") (pin "1") (pinfunction "1_1") (pintype "passive"))
    )
    (net (code "43") (name "Net-(CON1-Pad3)") (class "Default")
      (node (ref "CON1") (pin "3") (pinfunction "3_3") (pintype "passive"))
      (node (ref "MOV1") (pin "1") (pinfunction "1_1") (pintype "passive"))
      (node (ref "RL1") (pin "3") (pinfunction "3_3") (pintype "passive"))
      (node (ref "Rsub1") (pin "2") (pinfunction "2_2") (pintype "passive"))
    )
    (net (code "44") (name "Net-(CON2-Pad1)") (class "Default")
      (node (ref "CON2") (pin "1") (pinfunction "1_1") (pintype "passive"))
      (node (ref "RL2") (pin "2") (pinfunction "2_2") (pintype "passive"))
    )
    (net (code "45") (name "Net-(CON2-Pad2)") (class "Default")
      (node (ref "CON2") (pin "2") (pinfunction "2_2") (pintype "passive"))
      (node (ref "Csub2") (pin "2") (pinfunction "2_2") (pintype "passive"))
      (node (ref "MOV2") (pin "2") (pinfunction "2_2") (pintype "passive"))
      (node (ref "RL2") (pin "1") (pinfunction "1_1") (pintype "passive"))
    )
    (net (code "46") (name "Net-(CON2-Pad3)") (class "Default")
      (node (ref "CON2") (pin "3") (pinfunction "3_3") (pintype "passive"))
      (node (ref "MOV2") (pin "1") (pinfunction "1_1") (pintype "passive"))
      (node (ref "RL2") (pin "3") (pinfunction "3_3") (pintype "passive"))
      (node (ref "Rsub2") (pin "2") (pinfunction "2_2") (pintype "passive"))
    )
    (net (code "47") (name "Net-(CON3-Pad1)") (class "Default")
      (node (ref "CON3") (pin "1") (pinfunction "1_1") (pintype "passive"))
      (node (ref "RL3") (pin "2") (pinfunction "2_2") (pintype "passive"))
    )
    (net (code "48") (name "Net-(CON3-Pad2)") (class "Default")
      (node (ref "CON3") (pin "2") (pinfunction "2_2") (pintype "passive"))
      (node (ref "Csub3") (pin "2") (pinfunction "2_2") (pintype "passive"))
      (node (ref "MOV3") (pin "2") (pinfunction "2_2") (pintype "passive"))
      (node (ref "RL3") (pin "1") (pinfunction "1_1") (pintype "passive"))
    )
    (net (code "49") (name "Net-(CON3-Pad3)") (class "Default")
      (node (ref "CON3") (pin "3") (pinfunction "3_3") (pintype "passive"))
      (node (ref "MOV3") (pin "1") (pinfunction "1_1") (pintype "passive"))
      (node (ref "RL3") (pin "3") (pinfunction "3_3") (pintype "passive"))
      (node (ref "Rsub3") (pin "2") (pinfunction "2_2") (pintype "passive"))
    )
    (net (code "50") (name "Net-(CON4-Pad1)") (class "Default")
      (node (ref "CON4") (pin "1") (pinfunction "1_1") (pintype "passive"))
      (node (ref "RL4") (pin "2") (pinfunction "2_2") (pintype "passive"))
    )
    (net (code "51") (name "Net-(CON4-Pad2)") (class "Default")
      (node (ref "CON4") (pin "2") (pinfunction "2_2") (pintype "passive"))
      (node (ref "Csub4") (pin "2") (pinfunction "2_2") (pintype "passive"))
      (node (ref "MOV4") (pin "2") (pinfunction "2_2") (pintype "passive"))
      (node (ref "RL4") (pin "1") (pinfunction "1_1") (pintype "passive"))
    )
    (net (code "52") (name "Net-(CON4-Pad3)") (class "Default")
      (node (ref "CON4") (pin "3") (pinfunction "3_3") (pintype "passive"))
      (node (ref "MOV4") (pin "1") (pinfunction "1_1") (pintype "passive"))
      (node (ref "RL4") (pin "3") (pinfunction "3_3") (pintype "passive"))
      (node (ref "Rsub4") (pin "2") (pinfunction "2_2") (pintype "passive"))
    )
    (net (code "53") (name "Net-(CON5-Pad1)") (class "Default")
      (node (ref "CON5") (pin "1") (pinfunction "1_1") (pintype "passive"))
      (node (ref "RL5") (pin "2") (pinfunction "2_2") (pintype "passive"))
    )
    (net (code "54") (name "Net-(CON5-Pad2)") (class "Default")
      (node (ref "CON5") (pin "2") (pinfunction "2_2") (pintype "passive"))
      (node (ref "Csub5") (pin "2") (pinfunction "2_2") (pintype "passive"))
      (node (ref "MOV5") (pin "2") (pinfunction "2_2") (pintype "passive"))
      (node (ref "RL5") (pin "1") (pinfunction "1_1") (pintype "passive"))
    )
    (net (code "55") (name "Net-(CON5-Pad3)") (class "Default")
      (node (ref "CON5") (pin "3") (pinfunction "3_3") (pintype "passive"))
      (node (ref "MOV5") (pin "1") (pinfunction "1_1") (pintype "passive"))
      (node (ref "RL5") (pin "3") (pinfunction "3_3") (pintype "passive"))
      (node (ref "Rsub5") (pin "2") (pinfunction "2_2") (pintype "passive"))
    )
    (net (code "56") (name "Net-(CON6-Pad1)") (class "Default")
      (node (ref "CON6") (pin "1") (pinfunction "1_1") (pintype "passive"))
      (node (ref "RL6") (pin "2") (pinfunction "2_2") (pintype "passive"))
    )
    (net (code "57") (name "Net-(CON6-Pad2)") (class "Default")
      (node (ref "CON6") (pin "2") (pinfunction "2_2") (pintype "passive"))
      (node (ref "Csub6") (pin "2") (pinfunction "2_2") (pintype "passive"))
      (node (ref "MOV6") (pin "2") (pinfunction "2_2") (pintype "passive"))
      (node (ref "RL6") (pin "1") (pinfunction "1_1") (pintype "passive"))
    )
    (net (code "58") (name "Net-(CON6-Pad3)") (class "Default")
      (node (ref "CON6") (pin "3") (pinfunction "3_3") (pintype "passive"))
      (node (ref "MOV6") (pin "1") (pinfunction "1_1") (pintype "passive"))
      (node (ref "RL6") (pin "3") (pinfunction "3_3") (pintype "passive"))
      (node (ref "Rsub6") (pin "2") (pinfunction "2_2") (pintype "passive"))
    )
    (net (code "59") (name "Net-(CON7-Pad1)") (class "Default")
      (node (ref "CON7") (pin "1") (pinfunction "1_1") (pintype "passive"))
      (node (ref "RL7") (pin "2") (pinfunction "2_2") (pintype "passive"))
    )
    (net (code "60") (name "Net-(CON7-Pad2)") (class "Default")
      (node (ref "CON7") (pin "2") (pinfunction "2_2") (pintype "passive"))
      (node (ref "Csub7") (pin "2") (pinfunction "2_2") (pintype "passive"))
      (node (ref "MOV7") (pin "2") (pinfunction "2_2") (pintype "passive"))
      (node (ref "RL7") (pin "1") (pinfunction "1_1") (pintype "passive"))
    )
    (net (code "61") (name "Net-(CON7-Pad3)") (class "Default")
      (node (ref "CON7") (pin "3") (pinfunction "3_3") (pintype "passive"))
      (node (ref "MOV7") (pin "1") (pinfunction "1_1") (pintype "passive"))
      (node (ref "RL7") (pin "3") (pinfunction "3_3") (pintype "passive"))
      (node (ref "Rsub7") (pin "2") (pinfunction "2_2") (pintype "passive"))
    )
    (net (code "62") (name "Net-(CON8-Pad1)") (class "Default")
      (node (ref "CON8") (pin "1") (pinfunction "1_1") (pintype "passive"))
      (node (ref "RL8") (pin "2") (pinfunction "2_2") (pintype "passive"))
    )
    (net (code "63") (name "Net-(CON8-Pad2)") (class "Default")
      (node (ref "CON8") (pin "2") (pinfunction "2_2") (pintype "passive"))
      (node (ref "Csub8") (pin "2") (pinfunction "2_2") (pintype "passive"))
      (node (ref "MOV8") (pin "2") (pinfunction "2_2") (pintype "passive"))
      (node (ref "RL8") (pin "1") (pinfunction "1_1") (pintype "passive"))
    )
    (net (code "64") (name "Net-(CON8-Pad3)") (class "Default")
      (node (ref "CON8") (pin "3") (pinfunction "3_3") (pintype "passive"))
      (node (ref "MOV8") (pin "1") (pinfunction "1_1") (pintype "passive"))
      (node (ref "RL8") (pin "3") (pinfunction "3_3") (pintype "passive"))
      (node (ref "Rsub8") (pin "2") (pinfunction "2_2") (pintype "passive"))
    )
    (net (code "65") (name "Net-(Csub1-Pad1)") (class "Default")
      (node (ref "Csub1") (pin "1") (pinfunction "1_1") (pintype "passive"))
      (node (ref "Rsub1") (pin "1") (pinfunction "1_1") (pintype "passive"))
    )
    (net (code "66") (name "Net-(Csub2-Pad1)") (class "Default")
      (node (ref "Csub2") (pin "1") (pinfunction "1_1") (pintype "passive"))
      (node (ref "Rsub2") (pin "1") (pinfunction "1_1") (pintype "passive"))
    )
    (net (code "67") (name "Net-(Csub3-Pad1)") (class "Default")
      (node (ref "Csub3") (pin "1") (pinfunction "1_1") (pintype "passive"))
      (node (ref "Rsub3") (pin "1") (pinfunction "1_1") (pintype "passive"))
    )
    (net (code "68") (name "Net-(Csub4-Pad1)") (class "Default")
      (node (ref "Csub4") (pin "1") (pinfunction "1_1") (pintype "passive"))
      (node (ref "Rsub4") (pin "1") (pinfunction "1_1") (pintype "passive"))
    )
    (net (code "69") (name "Net-(Csub5-Pad1)") (class "Default")
      (node (ref "Csub5") (pin "1") (pinfunction "1_1") (pintype "passive"))
      (node (ref "Rsub5") (pin "1") (pinfunction "1_1") (pintype "passive"))
    )
    (net (code "70") (name "Net-(Csub6-Pad1)") (class "Default")
      (node (ref "Csub6") (pin "1") (pinfunction "1_1") (pintype "passive"))
      (node (ref "Rsub6") (pin "1") (pinfunction "1_1") (pintype "passive"))
    )
    (net (code "71") (name "Net-(Csub7-Pad1)") (class "Default")
      (node (ref "Csub7") (pin "1") (pinfunction "1_1") (pintype "passive"))
      (node (ref "Rsub7") (pin "1") (pinfunction "1_1") (pintype "passive"))
    )
    (net (code "72") (name "Net-(Csub8-Pad1)") (class "Default")
      (node (ref "Csub8") (pin "1") (pinfunction "1_1") (pintype "passive"))
      (node (ref "Rsub8") (pin "1") (pinfunction "1_1") (pintype "passive"))
    )
    (net (code "73") (name "Net-(D11-A)") (class "Default")
      (node (ref "D11") (pin "1") (pinfunction "A_1") (pintype "passive"))
      (node (ref "E1") (pin "K") (pinfunction "K_K") (pintype "passive"))
      (node (ref "Q11") (pin "2") (pinfunction "C_2") (pintype "passive"))
      (node (ref "RL1") (pin "4") (pinfunction "4_4") (pintype "passive"))
    )
    (net (code "74") (name "Net-(D12-A)") (class "Default")
      (node (ref "D12") (pin "1") (pinfunction "A_1") (pintype "passive"))
      (node (ref "E2") (pin "K") (pinfunction "K_K") (pintype "passive"))
      (node (ref "Q12") (pin "2") (pinfunction "C_2") (pintype "passive"))
      (node (ref "RL2") (pin "4") (pinfunction "4_4") (pintype "passive"))
    )
    (net (code "75") (name "Net-(D13-A)") (class "Default")
      (node (ref "D13") (pin "1") (pinfunction "A_1") (pintype "passive"))
      (node (ref "E3") (pin "K") (pinfunction "K_K") (pintype "passive"))
      (node (ref "Q13") (pin "2") (pinfunction "C_2") (pintype "passive"))
      (node (ref "RL3") (pin "4") (pinfunction "4_4") (pintype "passive"))
    )
    (net (code "76") (name "Net-(D14-A)") (class "Default")
      (node (ref "D14") (pin "1") (pinfunction "A_1") (pintype "passive"))
      (node (ref "E4") (pin "K") (pinfunction "K_K") (pintype "passive"))
      (node (ref "Q14") (pin "2") (pinfunction "C_2") (pintype "passive"))
      (node (ref "RL4") (pin "4") (pinfunction "4_4") (pintype "passive"))
    )
    (net (code "77") (name "Net-(D15-A)") (class "Default")
      (node (ref "D15") (pin "1") (pinfunction "A_1") (pintype "passive"))
      (node (ref "E5") (pin "K") (pinfunction "K_K") (pintype "passive"))
      (node (ref "Q15") (pin "2") (pinfunction "C_2") (pintype "passive"))
      (node (ref "RL5") (pin "4") (pinfunction "4_4") (pintype "passive"))
    )
    (net (code "78") (name "Net-(D16-A)") (class "Default")
      (node (ref "D16") (pin "1") (pinfunction "A_1") (pintype "passive"))
      (node (ref "E6") (pin "K") (pinfunction "K_K") (pintype "passive"))
      (node (ref "Q16") (pin "2") (pinfunction "C_2") (pintype "passive"))
      (node (ref "RL6") (pin "4") (pinfunction "4_4") (pintype "passive"))
    )
    (net (code "79") (name "Net-(D17-A)") (class "Default")
      (node (ref "D17") (pin "1") (pinfunction "A_1") (pintype "passive"))
      (node (ref "E7") (pin "K") (pinfunction "K_K") (pintype "passive"))
      (node (ref "Q17") (pin "2") (pinfunction "C_2") (pintype "passive"))
      (node (ref "RL7") (pin "4") (pinfunction "4_4") (pintype "passive"))
    )
    (net (code "80") (name "Net-(D18-A)") (class "Default")
      (node (ref "D18") (pin "1") (pinfunction "A_1") (pintype "passive"))
      (node (ref "E8") (pin "K") (pinfunction "K_K") (pintype "passive"))
      (node (ref "Q18") (pin "2") (pinfunction "C_2") (pintype "passive"))
      (node (ref "RL8") (pin "4") (pinfunction "4_4") (pintype "passive"))
    )
    (net (code "81") (name "Net-(D21-K)") (class "Default")
      (node (ref "12V_IN") (pin "1") (pinfunction "1_1") (pintype "passive"))
      (node (ref "D21") (pin "2") (pinfunction "K_2") (pintype "passive"))
      (node (ref "F21") (pin "1") (pinfunction "1_1") (pintype "passive"))
    )
    (net (code "82") (name "Net-(E1-PadA)") (class "Default")
      (node (ref "E1") (pin "A") (pinfunction "A_A") (pintype "passive"))
      (node (ref "Rrl13") (pin "1") (pinfunction "1_1") (pintype "passive"))
    )
    (net (code "83") (name "Net-(E2-PadA)") (class "Default")
      (node (ref "E2") (pin "A") (pinfunction "A_A") (pintype "passive"))
      (node (ref "Rrl23") (pin "1") (pinfunction "1_1") (pintype "passive"))
    )
    (net (code "84") (name "Net-(E3-PadA)") (class "Default")
      (node (ref "E3") (pin "A") (pinfunction "A_A") (pintype "passive"))
      (node (ref "Rrl33") (pin "1") (pinfunction "1_1") (pintype "passive"))
    )
    (net (code "85") (name "Net-(E4-PadA)") (class "Default")
      (node (ref "E4") (pin "A") (pinfunction "A_A") (pintype "passive"))
      (node (ref "Rrl43") (pin "1") (pinfunction "1_1") (pintype "passive"))
    )
    (net (code "86") (name "Net-(E5-PadA)") (class "Default")
      (node (ref "E5") (pin "A") (pinfunction "A_A") (pintype "passive"))
      (node (ref "Rrl53") (pin "1") (pinfunction "1_1") (pintype "passive"))
    )
    (net (code "87") (name "Net-(E6-PadA)") (class "Default")
      (node (ref "E6") (pin "A") (pinfunction "A_A") (pintype "passive"))
      (node (ref "Rrl63") (pin "1") (pinfunction "1_1") (pintype "passive"))
    )
    (net (code "88") (name "Net-(E7-PadA)") (class "Default")
      (node (ref "E7") (pin "A") (pinfunction "A_A") (pintype "passive"))
      (node (ref "Rrl73") (pin "1") (pinfunction "1_1") (pintype "passive"))
    )
    (net (code "89") (name "Net-(E8-PadA)") (class "Default")
      (node (ref "E8") (pin "A") (pinfunction "A_A") (pintype "passive"))
      (node (ref "Rrl83") (pin "1") (pinfunction "1_1") (pintype "passive"))
    )
    (net (code "90") (name "Net-(IN1A-A)") (class "Default")
      (node (ref "IN1") (pin "1") (pinfunction "A_1") (pintype "passive"))
      (node (ref "R01") (pin "1") (pinfunction "1_1") (pintype "passive"))
    )
    (net (code "91") (name "Net-(IN2A-A)") (class "Default")
      (node (ref "IN2") (pin "1") (pinfunction "A_1") (pintype "passive"))
      (node (ref "R03") (pin "1") (pinfunction "1_1") (pintype "passive"))
    )
    (net (code "92") (name "Net-(IN3A-A)") (class "Default")
      (node (ref "IN3") (pin "1") (pinfunction "A_1") (pintype "passive"))
      (node (ref "R05") (pin "1") (pinfunction "1_1") (pintype "passive"))
    )
    (net (code "93") (name "Net-(IN4A-A)") (class "Default")
      (node (ref "IN4") (pin "1") (pinfunction "A_1") (pintype "passive"))
      (node (ref "R07") (pin "1") (pinfunction "1_1") (pintype "passive"))
    )
    (net (code "94") (name "Net-(IN5A-A)") (class "Default")
      (node (ref "IN5") (pin "1") (pinfunction "A_1") (pintype "passive"))
      (node (ref "R09") (pin "1") (pinfunction "1_1") (pintype "passive"))
    )
    (net (code "95") (name "Net-(IN6A-A)") (class "Default")
      (node (ref "IN6") (pin "1") (pinfunction "A_1") (pintype "passive"))
      (node (ref "R11") (pin "1") (pinfunction "1_1") (pintype "passive"))
    )
    (net (code "96") (name "Net-(IN7A-A)") (class "Default")
      (node (ref "IN7") (pin "1") (pinfunction "A_1") (pintype "passive"))
      (node (ref "R13") (pin "1") (pinfunction "1_1") (pintype "passive"))
    )
    (net (code "97") (name "Net-(IN8A-A)") (class "Default")
      (node (ref "IN8") (pin "1") (pinfunction "A_1") (pintype "passive"))
      (node (ref "R15") (pin "1") (pinfunction "1_1") (pintype "passive"))
    )
    (net (code "98") (name "Net-(PW-K)") (class "Default")
      (node (ref "PW") (pin "2") (pinfunction "K_2") (pintype "passive"))
      (node (ref "R21") (pin "1") (pinfunction "1_1") (pintype "passive"))
    )
    (net (code "99") (name "Net-(Q11-B)") (class "Default")
      (node (ref "Q11") (pin "1") (pinfunction "B_1") (pintype "passive"))
      (node (ref "Rrl11") (pin "2") (pinfunction "2_2") (pintype "passive"))
      (node (ref "Rrl12") (pin "2") (pinfunction "2_2") (pintype "passive"))
    )
    (net (code "100") (name "Net-(Q12-B)") (class "Default")
      (node (ref "Q12") (pin "1") (pinfunction "B_1") (pintype "passive"))
      (node (ref "Rrl21") (pin "2") (pinfunction "2_2") (pintype "passive"))
      (node (ref "Rrl22") (pin "2") (pinfunction "2_2") (pintype "passive"))
    )
    (net (code "101") (name "Net-(Q13-B)") (class "Default")
      (node (ref "Q13") (pin "1") (pinfunction "B_1") (pintype "passive"))
      (node (ref "Rrl31") (pin "2") (pinfunction "2_2") (pintype "passive"))
      (node (ref "Rrl32") (pin "2") (pinfunction "2_2") (pintype "passive"))
    )
    (net (code "102") (name "Net-(Q14-B)") (class "Default")
      (node (ref "Q14") (pin "1") (pinfunction "B_1") (pintype "passive"))
      (node (ref "Rrl41") (pin "2") (pinfunction "2_2") (pintype "passive"))
      (node (ref "Rrl42") (pin "2") (pinfunction "2_2") (pintype "passive"))
    )
    (net (code "103") (name "Net-(Q15-B)") (class "Default")
      (node (ref "Q15") (pin "1") (pinfunction "B_1") (pintype "passive"))
      (node (ref "Rl52") (pin "2") (pinfunction "2_2") (pintype "passive"))
      (node (ref "Rrl51") (pin "2") (pinfunction "2_2") (pintype "passive"))
    )
    (net (code "104") (name "Net-(Q16-B)") (class "Default")
      (node (ref "Q16") (pin "1") (pinfunction "B_1") (pintype "passive"))
      (node (ref "Rrl61") (pin "2") (pinfunction "2_2") (pintype "passive"))
      (node (ref "Rrl62") (pin "2") (pinfunction "2_2") (pintype "passive"))
    )
    (net (code "105") (name "Net-(Q17-B)") (class "Default")
      (node (ref "Q17") (pin "1") (pinfunction "B_1") (pintype "passive"))
      (node (ref "Rrl71") (pin "2") (pinfunction "2_2") (pintype "passive"))
      (node (ref "Rrl72") (pin "2") (pinfunction "2_2") (pintype "passive"))
    )
    (net (code "106") (name "Net-(Q18-B)") (class "Default")
      (node (ref "Q18") (pin "1") (pinfunction "B_1") (pintype "passive"))
      (node (ref "Rrl81") (pin "2") (pinfunction "2_2") (pintype "passive"))
      (node (ref "Rrl82") (pin "2") (pinfunction "2_2") (pintype "passive"))
    )
    (net (code "107") (name "Net-(Run-K)") (class "Default")
      (node (ref "R31") (pin "1") (pinfunction "1_1") (pintype "passive"))
      (node (ref "Run") (pin "2") (pinfunction "K_2") (pintype "passive"))
    )
  )
)
